# ethernet.net
KiCad netlist of a schematic drawn in Altium Designer
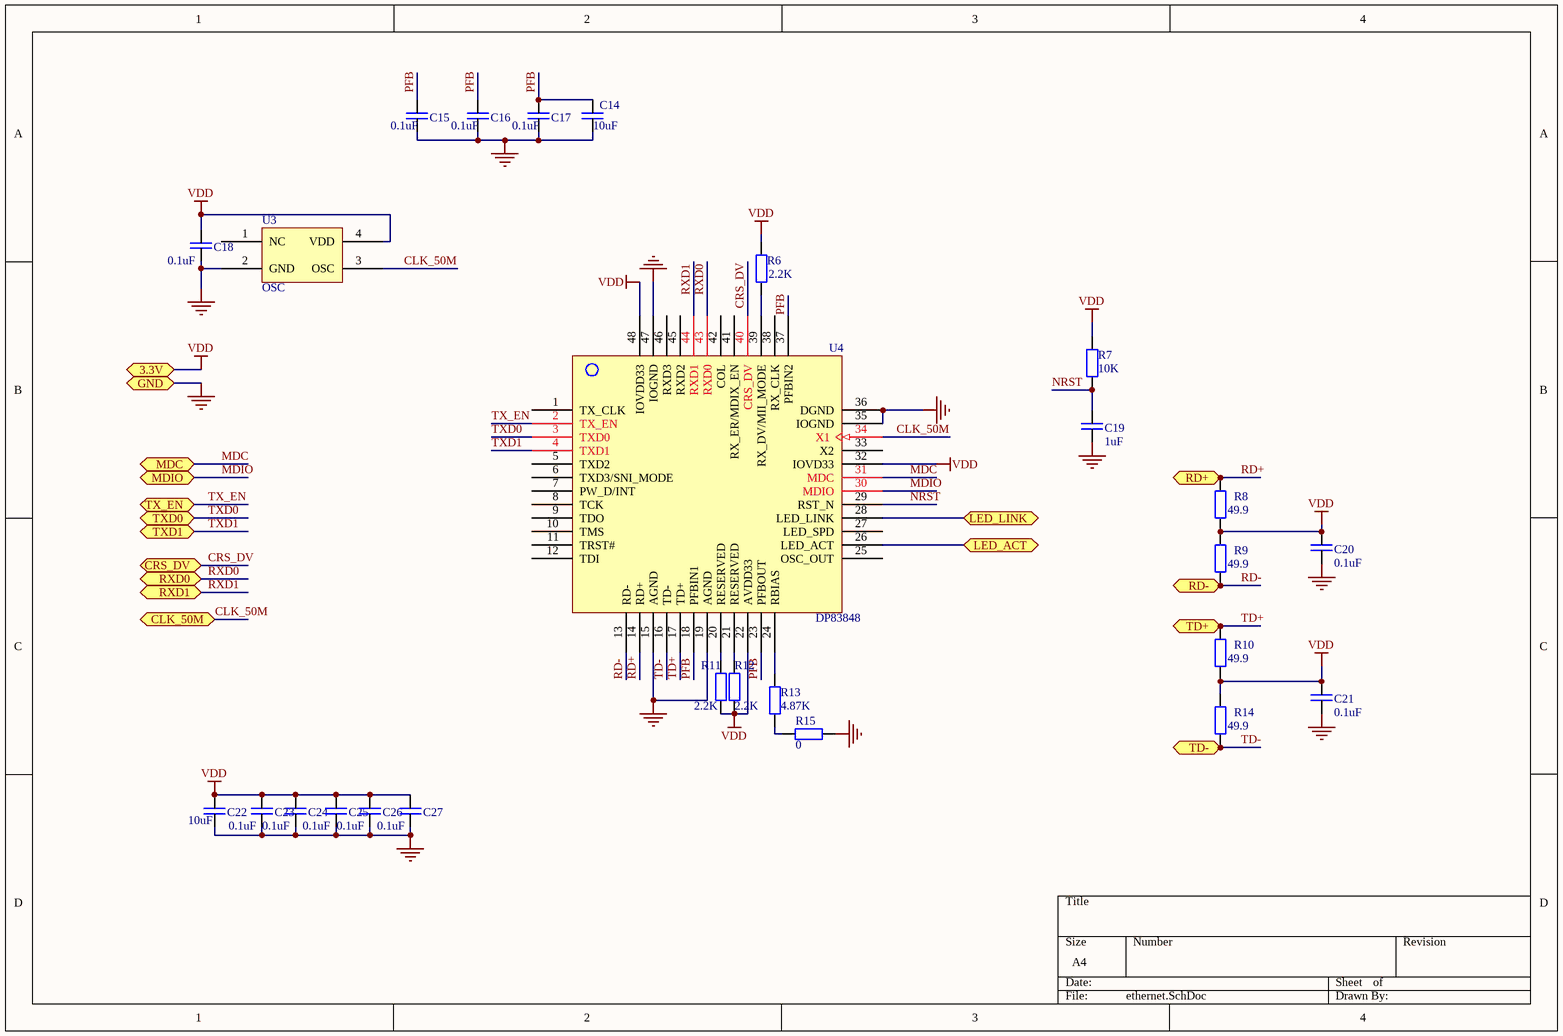
[diagram p0: ethernet.SchDoc]

(export (version "E")
  (design (tool "Eeschema 10.0.6"))
  (components
    (comp (ref "C14")
      (value "10uF")
      (footprint "CAP-0805")
      (fields (field (name "Comment") "CAP"))
      (libsource (lib "Schlib1") (part "CAP"))
    )
    (comp (ref "C15")
      (value "0.1uF")
      (footprint "CAP-0805")
      (fields (field (name "Comment") "CAP"))
      (libsource (lib "Schlib1") (part "CAP"))
    )
    (comp (ref "C16")
      (value "0.1uF")
      (footprint "CAP-0805")
      (fields (field (name "Comment") "CAP"))
      (libsource (lib "Schlib1") (part "CAP"))
    )
    (comp (ref "C17")
      (value "0.1uF")
      (footprint "CAP-0805")
      (fields (field (name "Comment") "CAP"))
      (libsource (lib "Schlib1") (part "CAP"))
    )
    (comp (ref "C18")
      (value "0.1uF")
      (footprint "CAP-0805")
      (fields (field (name "Comment") "CAP"))
      (libsource (lib "Schlib1") (part "CAP"))
    )
    (comp (ref "C19")
      (value "1uF")
      (footprint "CAP-0805")
      (fields (field (name "Comment") "CAP"))
      (libsource (lib "Schlib1") (part "CAP"))
    )
    (comp (ref "C20")
      (value "0.1uF")
      (footprint "CAP-0805")
      (fields (field (name "Comment") "CAP"))
      (libsource (lib "Schlib1") (part "CAP"))
    )
    (comp (ref "C21")
      (value "0.1uF")
      (footprint "CAP-0805")
      (fields (field (name "Comment") "CAP"))
      (libsource (lib "Schlib1") (part "CAP"))
    )
    (comp (ref "C22")
      (value "10uF")
      (footprint "CAP-0805")
      (fields (field (name "Comment") "CAP"))
      (libsource (lib "Schlib1") (part "CAP"))
    )
    (comp (ref "C23")
      (value "0.1uF")
      (footprint "CAP-0805")
      (fields (field (name "Comment") "CAP"))
      (libsource (lib "Schlib1") (part "CAP"))
    )
    (comp (ref "C24")
      (value "0.1uF")
      (footprint "CAP-0805")
      (fields (field (name "Comment") "CAP"))
      (libsource (lib "Schlib1") (part "CAP"))
    )
    (comp (ref "C25")
      (value "0.1uF")
      (footprint "CAP-0805")
      (fields (field (name "Comment") "CAP"))
      (libsource (lib "Schlib1") (part "CAP"))
    )
    (comp (ref "C26")
      (value "0.1uF")
      (footprint "CAP-0805")
      (fields (field (name "Comment") "CAP"))
      (libsource (lib "Schlib1") (part "CAP"))
    )
    (comp (ref "C27")
      (value "0.1uF")
      (footprint "CAP-0805")
      (fields (field (name "Comment") "CAP"))
      (libsource (lib "Schlib1") (part "CAP"))
    )
    (comp (ref "R6")
      (value "2.2K")
      (footprint "RES-0805")
      (fields (field (name "Comment") "RES"))
      (libsource (lib "Schlib1") (part "RES"))
    )
    (comp (ref "R7")
      (value "10K")
      (footprint "RES-0805")
      (fields (field (name "Comment") "RES"))
      (libsource (lib "Schlib1") (part "RES"))
    )
    (comp (ref "R8")
      (value "49.9")
      (footprint "RES-0805")
      (fields (field (name "Comment") "RES"))
      (libsource (lib "Schlib1") (part "RES"))
    )
    (comp (ref "R9")
      (value "49.9")
      (footprint "RES-0805")
      (fields (field (name "Comment") "RES"))
      (libsource (lib "Schlib1") (part "RES"))
    )
    (comp (ref "R10")
      (value "49.9")
      (footprint "RES-0805")
      (fields (field (name "Comment") "RES"))
      (libsource (lib "Schlib1") (part "RES"))
    )
    (comp (ref "R11")
      (value "2.2K")
      (footprint "RES-0805")
      (fields (field (name "Comment") "RES"))
      (libsource (lib "Schlib1") (part "RES"))
    )
    (comp (ref "R12")
      (value "2.2K")
      (footprint "RES-0805")
      (fields (field (name "Comment") "RES"))
      (libsource (lib "Schlib1") (part "RES"))
    )
    (comp (ref "R13")
      (value "4.87K")
      (footprint "RES-0805")
      (fields (field (name "Comment") "RES"))
      (libsource (lib "Schlib1") (part "RES"))
    )
    (comp (ref "R14")
      (value "49.9")
      (footprint "RES-0805")
      (fields (field (name "Comment") "RES"))
      (libsource (lib "Schlib1") (part "RES"))
    )
    (comp (ref "R15")
      (value "0")
      (footprint "RES-0805")
      (fields (field (name "Comment") "RES"))
      (libsource (lib "") (part "RES_1"))
    )
    (comp (ref "U3") (value "OSC") (footprint "OSC_S") (libsource (lib "Schlib1") (part "OSC")))
    (comp (ref "U4") (value "DP83848") (footprint "LQFP48") (libsource (lib "Schlib1") (part "DP83848")))
  )
  (nets
    (net (code "1") (name "/CLK_50M") (class "Default")
      (node (ref "U3") (pin "3") (pinfunction "OSC_3") (pintype "passive"))
      (node (ref "U4") (pin "34") (pinfunction "X1_34") (pintype "input"))
    )
    (net (code "2") (name "/CRS_DV") (class "Default")
      (node (ref "U4") (pin "40") (pinfunction "CRS_DV_40") (pintype "passive"))
    )
    (net (code "3") (name "/LED_ACT") (class "Default")
      (node (ref "U4") (pin "26") (pinfunction "LED_ACT_26") (pintype "passive"))
    )
    (net (code "4") (name "/LED_LINK") (class "Default")
      (node (ref "U4") (pin "28") (pinfunction "LED_LINK_28") (pintype "passive"))
    )
    (net (code "5") (name "/MDC") (class "Default")
      (node (ref "U4") (pin "31") (pinfunction "MDC_31") (pintype "passive"))
    )
    (net (code "6") (name "/MDIO") (class "Default")
      (node (ref "U4") (pin "30") (pinfunction "MDIO_30") (pintype "passive"))
    )
    (net (code "7") (name "/NRST") (class "Default")
      (node (ref "C19") (pin "2") (pintype "passive"))
      (node (ref "R7") (pin "1") (pintype "passive"))
      (node (ref "U4") (pin "29") (pinfunction "RST_N_29") (pintype "passive"))
    )
    (net (code "8") (name "/PFB") (class "Default")
      (node (ref "C14") (pin "2") (pintype "passive"))
      (node (ref "C15") (pin "2") (pintype "passive"))
      (node (ref "C16") (pin "2") (pintype "passive"))
      (node (ref "C17") (pin "2") (pintype "passive"))
      (node (ref "U4") (pin "18") (pinfunction "PFBIN1_18") (pintype "passive"))
      (node (ref "U4") (pin "23") (pinfunction "PFBOUT_23") (pintype "passive"))
      (node (ref "U4") (pin "37") (pinfunction "PFBIN2_37") (pintype "passive"))
    )
    (net (code "9") (name "/RD+") (class "Default")
      (node (ref "R8") (pin "2") (pintype "passive"))
      (node (ref "U4") (pin "14") (pinfunction "RD+_14") (pintype "passive"))
    )
    (net (code "10") (name "/RD-") (class "Default")
      (node (ref "R9") (pin "1") (pintype "passive"))
      (node (ref "U4") (pin "13") (pinfunction "RD-_13") (pintype "passive"))
    )
    (net (code "11") (name "/RXD0") (class "Default")
      (node (ref "U4") (pin "43") (pinfunction "RXD0_43") (pintype "passive"))
    )
    (net (code "12") (name "/RXD1") (class "Default")
      (node (ref "U4") (pin "44") (pinfunction "RXD1_44") (pintype "passive"))
    )
    (net (code "13") (name "/TD+") (class "Default")
      (node (ref "R10") (pin "2") (pintype "passive"))
      (node (ref "U4") (pin "17") (pinfunction "TD+_17") (pintype "passive"))
    )
    (net (code "14") (name "/TD-") (class "Default")
      (node (ref "R14") (pin "1") (pintype "passive"))
      (node (ref "U4") (pin "16") (pinfunction "TD-_16") (pintype "passive"))
    )
    (net (code "15") (name "/TXD0") (class "Default")
      (node (ref "U4") (pin "3") (pinfunction "TXD0_3") (pintype "passive"))
    )
    (net (code "16") (name "/TXD1") (class "Default")
      (node (ref "U4") (pin "4") (pinfunction "TXD1_4") (pintype "passive"))
    )
    (net (code "17") (name "/TX_EN") (class "Default")
      (node (ref "U4") (pin "2") (pinfunction "TX_EN_2") (pintype "passive"))
    )
    (net (code "18") (name "GND") (class "Default")
      (node (ref "C14") (pin "1") (pintype "passive"))
      (node (ref "C15") (pin "1") (pintype "passive"))
      (node (ref "C16") (pin "1") (pintype "passive"))
      (node (ref "C17") (pin "1") (pintype "passive"))
      (node (ref "C18") (pin "1") (pintype "passive"))
      (node (ref "C19") (pin "1") (pintype "passive"))
      (node (ref "C20") (pin "1") (pintype "passive"))
      (node (ref "C21") (pin "1") (pintype "passive"))
      (node (ref "C22") (pin "1") (pintype "passive"))
      (node (ref "C23") (pin "1") (pintype "passive"))
      (node (ref "C24") (pin "1") (pintype "passive"))
      (node (ref "C25") (pin "1") (pintype "passive"))
      (node (ref "C26") (pin "1") (pintype "passive"))
      (node (ref "C27") (pin "1") (pintype "passive"))
      (node (ref "R15") (pin "1") (pintype "passive"))
      (node (ref "U3") (pin "2") (pinfunction "GND_2") (pintype "passive"))
      (node (ref "U4") (pin "15") (pinfunction "AGND_15") (pintype "passive"))
      (node (ref "U4") (pin "19") (pinfunction "AGND_19") (pintype "passive"))
      (node (ref "U4") (pin "35") (pinfunction "IOGND_35") (pintype "passive"))
      (node (ref "U4") (pin "36") (pinfunction "DGND_36") (pintype "passive"))
      (node (ref "U4") (pin "47") (pinfunction "IOGND_47") (pintype "passive"))
    )
    (net (code "19") (name "Net-(R11-Pad2)") (class "Default")
      (node (ref "R11") (pin "2") (pintype "passive"))
      (node (ref "U4") (pin "20") (pinfunction "RESERVED_20") (pintype "passive"))
    )
    (net (code "20") (name "Net-(R12-Pad2)") (class "Default")
      (node (ref "R12") (pin "2") (pintype "passive"))
      (node (ref "U4") (pin "21") (pinfunction "RESERVED_21") (pintype "passive"))
    )
    (net (code "21") (name "Net-(R13-Pad1)") (class "Default")
      (node (ref "R13") (pin "1") (pintype "passive"))
      (node (ref "R15") (pin "2") (pintype "passive"))
    )
    (net (code "22") (name "Net-(U4-RBIAS)") (class "Default")
      (node (ref "R13") (pin "2") (pintype "passive"))
      (node (ref "U4") (pin "24") (pinfunction "RBIAS_24") (pintype "passive"))
    )
    (net (code "23") (name "Net-(U4-RX_DV{slash}MII_MODE)") (class "Default")
      (node (ref "R6") (pin "1") (pintype "passive"))
      (node (ref "U4") (pin "39") (pinfunction "RX_DV/MII_MODE_39") (pintype "passive"))
    )
    (net (code "24") (name "VDD") (class "Default")
      (node (ref "C18") (pin "2") (pintype "passive"))
      (node (ref "C20") (pin "2") (pintype "passive"))
      (node (ref "C21") (pin "2") (pintype "passive"))
      (node (ref "C22") (pin "2") (pintype "passive"))
      (node (ref "C23") (pin "2") (pintype "passive"))
      (node (ref "C24") (pin "2") (pintype "passive"))
      (node (ref "C25") (pin "2") (pintype "passive"))
      (node (ref "C26") (pin "2") (pintype "passive"))
      (node (ref "C27") (pin "2") (pintype "passive"))
      (node (ref "R10") (pin "1") (pintype "passive"))
      (node (ref "R11") (pin "1") (pintype "passive"))
      (node (ref "R12") (pin "1") (pintype "passive"))
      (node (ref "R14") (pin "2") (pintype "passive"))
      (node (ref "R6") (pin "2") (pintype "passive"))
      (node (ref "R7") (pin "2") (pintype "passive"))
      (node (ref "R8") (pin "1") (pintype "passive"))
      (node (ref "R9") (pin "2") (pintype "passive"))
      (node (ref "U3") (pin "4") (pinfunction "VDD_4") (pintype "passive"))
      (node (ref "U4") (pin "22") (pinfunction "AVDD33_22") (pintype "passive"))
      (node (ref "U4") (pin "32") (pinfunction "IOVD33_32") (pintype "passive"))
      (node (ref "U4") (pin "48") (pinfunction "IOVDD33_48") (pintype "passive"))
    )
    (net (code "25") (name "unconnected-(U3-NC-Pad1)") (class "Default")
      (node (ref "U3") (pin "1") (pinfunction "NC_1") (pintype "passive"))
    )
    (net (code "26") (name "unconnected-(U4-COL-Pad42)") (class "Default")
      (node (ref "U4") (pin "42") (pinfunction "COL_42") (pintype "passive"))
    )
    (net (code "27") (name "unconnected-(U4-LED_SPD-Pad27)") (class "Default")
      (node (ref "U4") (pin "27") (pinfunction "LED_SPD_27") (pintype "passive"))
    )
    (net (code "28") (name "unconnected-(U4-OSC_OUT-Pad25)") (class "Default")
      (node (ref "U4") (pin "25") (pinfunction "OSC_OUT_25") (pintype "passive"))
    )
    (net (code "29") (name "unconnected-(U4-PW_D{slash}INT-Pad7)") (class "Default")
      (node (ref "U4") (pin "7") (pinfunction "PW_D/INT_7") (pintype "passive"))
    )
    (net (code "30") (name "unconnected-(U4-RXD2-Pad45)") (class "Default")
      (node (ref "U4") (pin "45") (pinfunction "RXD2_45") (pintype "passive"))
    )
    (net (code "31") (name "unconnected-(U4-RXD3-Pad46)") (class "Default")
      (node (ref "U4") (pin "46") (pinfunction "RXD3_46") (pintype "passive"))
    )
    (net (code "32") (name "unconnected-(U4-RX_CLK-Pad38)") (class "Default")
      (node (ref "U4") (pin "38") (pinfunction "RX_CLK_38") (pintype "passive"))
    )
    (net (code "33") (name "unconnected-(U4-RX_ER{slash}MDIX_EN-Pad41)") (class "Default")
      (node (ref "U4") (pin "41") (pinfunction "RX_ER/MDIX_EN_41") (pintype "passive"))
    )
    (net (code "34") (name "unconnected-(U4-TCK-Pad8)") (class "Default")
      (node (ref "U4") (pin "8") (pinfunction "TCK_8") (pintype "passive"))
    )
    (net (code "35") (name "unconnected-(U4-TDI-Pad12)") (class "Default")
      (node (ref "U4") (pin "12") (pinfunction "TDI_12") (pintype "passive"))
    )
    (net (code "36") (name "unconnected-(U4-TDO-Pad9)") (class "Default")
      (node (ref "U4") (pin "9") (pinfunction "TDO_9") (pintype "passive"))
    )
    (net (code "37") (name "unconnected-(U4-TMS-Pad10)") (class "Default")
      (node (ref "U4") (pin "10") (pinfunction "TMS_10") (pintype "passive"))
    )
    (net (code "38") (name "unconnected-(U4-TRST#-Pad11)") (class "Default")
      (node (ref "U4") (pin "11") (pinfunction "TRST#_11") (pintype "passive"))
    )
    (net (code "39") (name "unconnected-(U4-TXD2-Pad5)") (class "Default")
      (node (ref "U4") (pin "5") (pinfunction "TXD2_5") (pintype "passive"))
    )
    (net (code "40") (name "unconnected-(U4-TXD3{slash}SNI_MODE-Pad6)") (class "Default")
      (node (ref "U4") (pin "6") (pinfunction "TXD3/SNI_MODE_6") (pintype "passive"))
    )
    (net (code "41") (name "unconnected-(U4-TX_CLK-Pad1)") (class "Default")
      (node (ref "U4") (pin "1") (pinfunction "TX_CLK_1") (pintype "passive"))
    )
    (net (code "42") (name "unconnected-(U4-X2-Pad33)") (class "Default")
      (node (ref "U4") (pin "33") (pinfunction "X2_33") (pintype "passive"))
    )
  )
)
